# CSM32RV20_TSSOP20_V1_1.net
KiCad netlist of a schematic drawn in Altium Designer
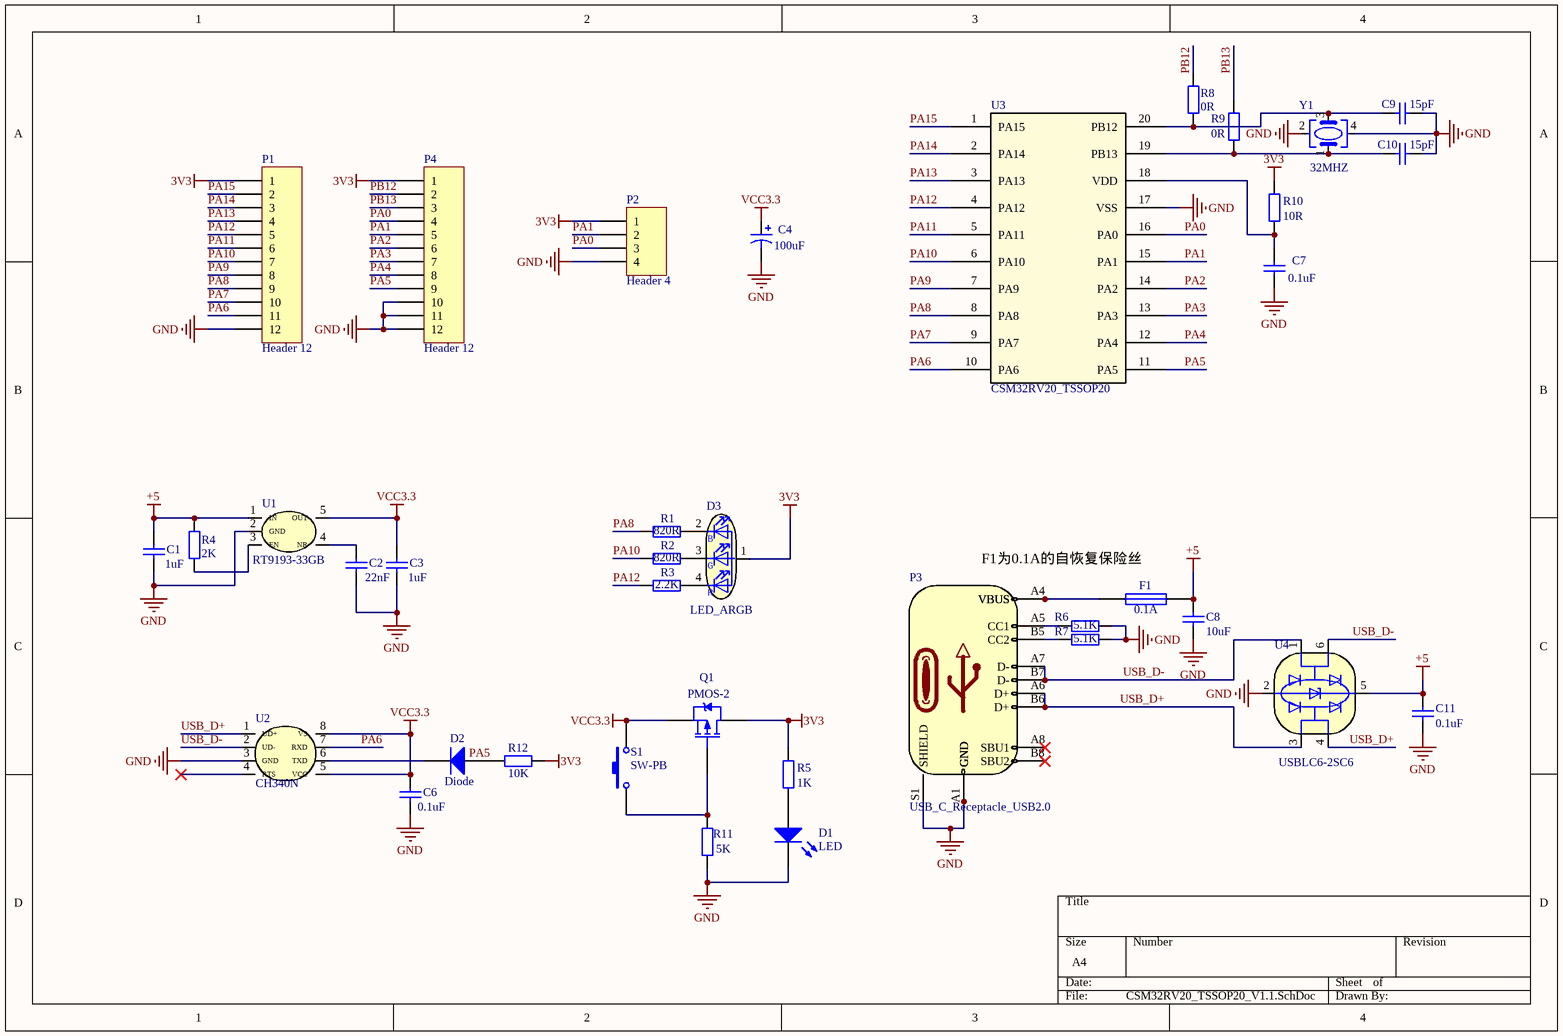
[diagram p0: CSM32RV20_TSSOP20_V1.1.SchDoc]

(export (version "E")
  (design (tool "Eeschema 10.0.6"))
  (components
    (comp (ref "C1")
      (value "1uF")
      (footprint "0402")
      (description "Capacitor")
      (fields (field (name "PUBLISHER") "Altium Limited"))
      (libsource (lib "Miscellaneous Devices") (part "Cap"))
    )
    (comp (ref "C2")
      (value "22nF")
      (footprint "0402")
      (description "Capacitor")
      (fields (field (name "PUBLISHER") "Altium Limited"))
      (libsource (lib "Miscellaneous Devices") (part "Cap"))
    )
    (comp (ref "C3")
      (value "1uF")
      (footprint "0402")
      (description "Capacitor")
      (fields (field (name "PUBLISHER") "Altium Limited"))
      (libsource (lib "Miscellaneous Devices") (part "Cap"))
    )
    (comp (ref "C4")
      (value "100uF")
      (footprint "C1210")
      (description "Polarized Capacitor (Surface Mount)")
      (fields (field (name "PUBLISHER") "Altium Limited"))
      (libsource (lib "Miscellaneous Devices") (part "Cap Pol3"))
    )
    (comp (ref "C6")
      (value "0.1uF")
      (footprint "0402")
      (description "Capacitor")
      (fields (field (name "PUBLISHER") "Altium Limited"))
      (libsource (lib "Miscellaneous Devices") (part "Cap"))
    )
    (comp (ref "C7")
      (value "0.1uF")
      (footprint "0402")
      (description "Capacitor")
      (fields (field (name "PUBLISHER") "Altium Limited"))
      (libsource (lib "Miscellaneous Devices") (part "Cap"))
    )
    (comp (ref "C8")
      (value "10uF")
      (footprint "0402")
      (description "Capacitor")
      (fields (field (name "PUBLISHER") "Altium Limited"))
      (libsource (lib "Miscellaneous Devices") (part "Cap"))
    )
    (comp (ref "C9")
      (value "15pF")
      (footprint "0402")
      (description "Capacitor")
      (fields (field (name "PUBLISHER") "Altium Limited"))
      (libsource (lib "Miscellaneous Devices") (part "Cap"))
    )
    (comp (ref "C10")
      (value "15pF")
      (footprint "0402")
      (description "Capacitor")
      (fields (field (name "PUBLISHER") "Altium Limited"))
      (libsource (lib "Miscellaneous Devices") (part "Cap"))
    )
    (comp (ref "C11")
      (value "0.1uF")
      (footprint "0402")
      (description "Capacitor")
      (fields (field (name "PUBLISHER") "Altium Limited"))
      (libsource (lib "Miscellaneous Devices") (part "Cap"))
    )
    (comp (ref "D1")
      (value "LED")
      (footprint "LED 0402")
      (description "Typical INFRARED GaAs LED")
      (fields (field (name "PUBLISHER") "Altium Limited"))
      (libsource (lib "Miscellaneous Devices") (part "LED0"))
    )
    (comp (ref "D2")
      (value "Diode")
      (footprint "D_SOD-123")
      (description "Default Diode")
      (fields (field (name "PUBLISHER") "Altium Limited"))
      (libsource (lib "Miscellaneous Devices") (part "Diode"))
    )
    (comp (ref "D3")
      (value "LED_ARGB")
      (footprint "LED_RGB_1210")
      (libsource (lib "YYT_library") (part "LED_ARGB"))
    )
    (comp (ref "F1")
      (value "0.1A")
      (footprint "C0805")
      (description "Fuse")
      (fields (field (name "PUBLISHER") "Altium Limited"))
      (libsource (lib "Miscellaneous Devices") (part "Fuse 1"))
    )
    (comp (ref "P1")
      (value "Header 12")
      (footprint "HDR1X12")
      (description "Header, 12-Pin")
      (fields (field (name "PUBLISHER") "Altium Limited"))
      (libsource (lib "Miscellaneous Connectors") (part "Header 12"))
    )
    (comp (ref "P2")
      (value "Header 4")
      (footprint "HDR1X4")
      (description "Header, 4-Pin")
      (fields (field (name "PUBLISHER") "Altium Limited"))
      (libsource (lib "Miscellaneous Connectors") (part "Header 4"))
    )
    (comp (ref "P3")
      (value "USB_C_Receptacle_USB2.0")
      (footprint "USB-C-SMD_KH-TYPE-C-16P")
      (libsource (lib "YYT_library") (part "USB_C_Receptacle_USB2.0"))
    )
    (comp (ref "P4")
      (value "Header 12")
      (footprint "HDR1X12")
      (description "Header, 12-Pin")
      (fields (field (name "PUBLISHER") "Altium Limited"))
      (libsource (lib "Miscellaneous Connectors") (part "Header 12"))
    )
    (comp (ref "Q1")
      (value "PMOS-2")
      (footprint "SOT-23")
      (description "P-Channel Power MOSFET")
      (fields (field (name "PUBLISHER") "Altium Limited"))
      (libsource (lib "YYT_library") (part "PMOS-2"))
    )
    (comp (ref "R1")
      (value "820R")
      (footprint "0402")
      (description "Resistor")
      (fields (field (name "PUBLISHER") "Altium Limited"))
      (libsource (lib "Miscellaneous Devices") (part "Res2"))
    )
    (comp (ref "R2")
      (value "820R")
      (footprint "0402")
      (description "Resistor")
      (fields (field (name "PUBLISHER") "Altium Limited"))
      (libsource (lib "Miscellaneous Devices") (part "Res2"))
    )
    (comp (ref "R3")
      (value "2.2K")
      (footprint "0402")
      (description "Resistor")
      (fields (field (name "PUBLISHER") "Altium Limited"))
      (libsource (lib "Miscellaneous Devices") (part "Res2"))
    )
    (comp (ref "R4")
      (value "2K")
      (footprint "0402")
      (description "Resistor")
      (fields (field (name "PUBLISHER") "Altium Limited"))
      (libsource (lib "") (part "Res2_1"))
    )
    (comp (ref "R5")
      (value "1K")
      (footprint "0402")
      (description "Resistor")
      (fields (field (name "PUBLISHER") "Altium Limited"))
      (libsource (lib "") (part "Res2_1"))
    )
    (comp (ref "R6")
      (value "5.1K")
      (footprint "0402")
      (description "Resistor")
      (fields (field (name "PUBLISHER") "Altium Limited"))
      (libsource (lib "Miscellaneous Devices") (part "Res2"))
    )
    (comp (ref "R7")
      (value "5.1K")
      (footprint "0402")
      (description "Resistor")
      (fields (field (name "PUBLISHER") "Altium Limited"))
      (libsource (lib "Miscellaneous Devices") (part "Res2"))
    )
    (comp (ref "R8")
      (value "0R")
      (footprint "0402")
      (description "Resistor")
      (fields (field (name "PUBLISHER") "Altium Limited"))
      (libsource (lib "") (part "Res2_1"))
    )
    (comp (ref "R9")
      (value "0R")
      (footprint "0402")
      (description "Resistor")
      (fields (field (name "PUBLISHER") "Altium Limited"))
      (libsource (lib "") (part "Res2_1"))
    )
    (comp (ref "R10")
      (value "10R")
      (footprint "0402")
      (description "Resistor")
      (fields (field (name "PUBLISHER") "Altium Limited"))
      (libsource (lib "") (part "Res2_1"))
    )
    (comp (ref "R11")
      (value "5K")
      (footprint "0402")
      (description "Resistor")
      (fields (field (name "PUBLISHER") "Altium Limited"))
      (libsource (lib "") (part "Res2_1"))
    )
    (comp (ref "R12")
      (value "10K")
      (footprint "0402")
      (description "Resistor")
      (fields (field (name "PUBLISHER") "Altium Limited"))
      (libsource (lib "Miscellaneous Devices") (part "Res2"))
    )
    (comp (ref "S1")
      (value "SW-PB")
      (footprint "SW_PUSH_SPST_NO_ALPS_SKRK")
      (description "Switch")
      (fields (field (name "PUBLISHER") "Altium Limited"))
      (libsource (lib "Miscellaneous Devices") (part "SW-PB"))
    )
    (comp (ref "U1")
      (value "RT9193-33GB")
      (footprint "SOT-23-5")
      (libsource (lib "YYT_library") (part "RT9193-33GB"))
    )
    (comp (ref "U2")
      (value "CH340N")
      (footprint "SOP-8-1EP_6X5MM_P1.27MM")
      (libsource (lib "YYT_library") (part "CH340N"))
    )
    (comp (ref "U3")
      (value "CSM32RV20_TSSOP20")
      (footprint "CSM32RV20_TSSOP20")
      (libsource (lib "YYT_library") (part "CSM32RV20_TSSOP20_1"))
    )
    (comp (ref "U4")
      (value "USBLC6-2SC6")
      (footprint "SOT-23-6")
      (libsource (lib "YYT_library") (part "USBLC6-2SC6"))
    )
    (comp (ref "Y1")
      (value "32MHZ")
      (footprint "CRYSTAL_SMD_3225-4PIN_3.2X2.5MM")
      (libsource (lib "YYT_library") (part "Crystal"))
    )
  )
  (nets
    (net (code "1") (name "+5") (class "Default")
      (node (ref "C1") (pin "2") (pinfunction "2_2") (pintype "passive"))
      (node (ref "C11") (pin "2") (pinfunction "2_2") (pintype "passive"))
      (node (ref "C8") (pin "2") (pinfunction "2_2") (pintype "passive"))
      (node (ref "F1") (pin "2") (pinfunction "2_2") (pintype "passive"))
      (node (ref "R4") (pin "2") (pinfunction "2_2") (pintype "passive"))
      (node (ref "U1") (pin "1") (pinfunction "IN_1") (pintype "passive"))
      (node (ref "U4") (pin "5") (pinfunction "VBUS_5") (pintype "passive"))
    )
    (net (code "2") (name "/PA0") (class "Default")
      (node (ref "P2") (pin "3") (pinfunction "3_3") (pintype "passive"))
      (node (ref "P4") (pin "4") (pinfunction "4_4") (pintype "passive"))
      (node (ref "U3") (pin "16") (pinfunction "PA0_16") (pintype "passive"))
    )
    (net (code "3") (name "/PA1") (class "Default")
      (node (ref "P2") (pin "2") (pinfunction "2_2") (pintype "passive"))
      (node (ref "P4") (pin "5") (pinfunction "5_5") (pintype "passive"))
      (node (ref "U3") (pin "15") (pinfunction "PA1_15") (pintype "passive"))
    )
    (net (code "4") (name "/PA2") (class "Default")
      (node (ref "P4") (pin "6") (pinfunction "6_6") (pintype "passive"))
      (node (ref "U3") (pin "14") (pinfunction "PA2_14") (pintype "passive"))
    )
    (net (code "5") (name "/PA3") (class "Default")
      (node (ref "P4") (pin "7") (pinfunction "7_7") (pintype "passive"))
      (node (ref "U3") (pin "13") (pinfunction "PA3_13") (pintype "passive"))
    )
    (net (code "6") (name "/PA4") (class "Default")
      (node (ref "P4") (pin "8") (pinfunction "8_8") (pintype "passive"))
      (node (ref "U3") (pin "12") (pinfunction "PA4_12") (pintype "passive"))
    )
    (net (code "7") (name "/PA5") (class "Default")
      (node (ref "D2") (pin "1") (pinfunction "A_1") (pintype "passive"))
      (node (ref "P4") (pin "9") (pinfunction "9_9") (pintype "passive"))
      (node (ref "R12") (pin "1") (pinfunction "1_1") (pintype "passive"))
      (node (ref "U3") (pin "11") (pinfunction "PA5_11") (pintype "passive"))
    )
    (net (code "8") (name "/PA6") (class "Default")
      (node (ref "P1") (pin "11") (pinfunction "11_11") (pintype "passive"))
      (node (ref "U2") (pin "7") (pinfunction "RXD_7") (pintype "passive"))
      (node (ref "U3") (pin "10") (pinfunction "PA6_10") (pintype "passive"))
    )
    (net (code "9") (name "/PA7") (class "Default")
      (node (ref "P1") (pin "10") (pinfunction "10_10") (pintype "passive"))
      (node (ref "U3") (pin "9") (pinfunction "PA7_9") (pintype "passive"))
    )
    (net (code "10") (name "/PA8") (class "Default")
      (node (ref "P1") (pin "9") (pinfunction "9_9") (pintype "passive"))
      (node (ref "R1") (pin "1") (pinfunction "1_1") (pintype "passive"))
      (node (ref "U3") (pin "8") (pinfunction "PA8_8") (pintype "passive"))
    )
    (net (code "11") (name "/PA9") (class "Default")
      (node (ref "P1") (pin "8") (pinfunction "8_8") (pintype "passive"))
      (node (ref "U3") (pin "7") (pinfunction "PA9_7") (pintype "passive"))
    )
    (net (code "12") (name "/PA10") (class "Default")
      (node (ref "P1") (pin "7") (pinfunction "7_7") (pintype "passive"))
      (node (ref "R2") (pin "1") (pinfunction "1_1") (pintype "passive"))
      (node (ref "U3") (pin "6") (pinfunction "PA10_6") (pintype "passive"))
    )
    (net (code "13") (name "/PA11") (class "Default")
      (node (ref "P1") (pin "6") (pinfunction "6_6") (pintype "passive"))
      (node (ref "U3") (pin "5") (pinfunction "PA11_5") (pintype "passive"))
    )
    (net (code "14") (name "/PA12") (class "Default")
      (node (ref "P1") (pin "5") (pinfunction "5_5") (pintype "passive"))
      (node (ref "R3") (pin "1") (pinfunction "1_1") (pintype "passive"))
      (node (ref "U3") (pin "4") (pinfunction "PA12_4") (pintype "passive"))
    )
    (net (code "15") (name "/PA13") (class "Default")
      (node (ref "P1") (pin "4") (pinfunction "4_4") (pintype "passive"))
      (node (ref "U3") (pin "3") (pinfunction "PA13_3") (pintype "passive"))
    )
    (net (code "16") (name "/PA14") (class "Default")
      (node (ref "P1") (pin "3") (pinfunction "3_3") (pintype "passive"))
      (node (ref "U3") (pin "2") (pinfunction "PA14_2") (pintype "passive"))
    )
    (net (code "17") (name "/PA15") (class "Default")
      (node (ref "P1") (pin "2") (pinfunction "2_2") (pintype "passive"))
      (node (ref "U3") (pin "1") (pinfunction "PA15_1") (pintype "passive"))
    )
    (net (code "18") (name "/PB12") (class "Default")
      (node (ref "P4") (pin "2") (pinfunction "2_2") (pintype "passive"))
      (node (ref "R8") (pin "2") (pinfunction "2_2") (pintype "passive"))
    )
    (net (code "19") (name "/PB13") (class "Default")
      (node (ref "P4") (pin "3") (pinfunction "3_3") (pintype "passive"))
      (node (ref "R9") (pin "2") (pinfunction "2_2") (pintype "passive"))
    )
    (net (code "20") (name "/USB_D+") (class "Default")
      (node (ref "P3") (pin "A6") (pinfunction "D+_A6") (pintype "passive"))
      (node (ref "P3") (pin "B6") (pinfunction "D+_B6") (pintype "passive"))
      (node (ref "U2") (pin "1") (pinfunction "UD+_1") (pintype "passive"))
      (node (ref "U4") (pin "3") (pinfunction "I/O2_3") (pintype "passive"))
      (node (ref "U4") (pin "4") (pinfunction "I/O2_4") (pintype "passive"))
    )
    (net (code "21") (name "/USB_D-") (class "Default")
      (node (ref "P3") (pin "A7") (pinfunction "D-_A7") (pintype "passive"))
      (node (ref "P3") (pin "B7") (pinfunction "D-_B7") (pintype "passive"))
      (node (ref "U2") (pin "2") (pinfunction "UD-_2") (pintype "passive"))
      (node (ref "U4") (pin "1") (pinfunction "I/O1_1") (pintype "passive"))
      (node (ref "U4") (pin "6") (pinfunction "I/O1_6") (pintype "passive"))
    )
    (net (code "22") (name "3V3") (class "Default")
      (node (ref "D3") (pin "1") (pinfunction "A_1") (pintype "passive"))
      (node (ref "P1") (pin "1") (pinfunction "1_1") (pintype "passive"))
      (node (ref "P2") (pin "1") (pinfunction "1_1") (pintype "passive"))
      (node (ref "P4") (pin "1") (pinfunction "1_1") (pintype "passive"))
      (node (ref "Q1") (pin "3") (pinfunction "D_3") (pintype "passive"))
      (node (ref "R10") (pin "2") (pinfunction "2_2") (pintype "passive"))
      (node (ref "R12") (pin "2") (pinfunction "2_2") (pintype "passive"))
      (node (ref "R5") (pin "2") (pinfunction "2_2") (pintype "passive"))
    )
    (net (code "23") (name "GND") (class "Default")
      (node (ref "C1") (pin "1") (pinfunction "1_1") (pintype "passive"))
      (node (ref "C10") (pin "2") (pinfunction "2_2") (pintype "passive"))
      (node (ref "C11") (pin "1") (pinfunction "1_1") (pintype "passive"))
      (node (ref "C2") (pin "1") (pinfunction "1_1") (pintype "passive"))
      (node (ref "C3") (pin "1") (pinfunction "1_1") (pintype "passive"))
      (node (ref "C4") (pin "2") (pinfunction "2_2") (pintype "passive"))
      (node (ref "C6") (pin "1") (pinfunction "1_1") (pintype "passive"))
      (node (ref "C7") (pin "1") (pinfunction "1_1") (pintype "passive"))
      (node (ref "C8") (pin "1") (pinfunction "1_1") (pintype "passive"))
      (node (ref "C9") (pin "2") (pinfunction "2_2") (pintype "passive"))
      (node (ref "D1") (pin "2") (pinfunction "K_2") (pintype "passive"))
      (node (ref "P1") (pin "12") (pinfunction "12_12") (pintype "passive"))
      (node (ref "P2") (pin "4") (pinfunction "4_4") (pintype "passive"))
      (node (ref "P3") (pin "A1") (pinfunction "GND_A1") (pintype "passive"))
      (node (ref "P3") (pin "A12") (pinfunction "GND_A12") (pintype "passive"))
      (node (ref "P3") (pin "B1") (pinfunction "GND_B1") (pintype "passive"))
      (node (ref "P3") (pin "B12") (pinfunction "GND_B12") (pintype "passive"))
      (node (ref "P3") (pin "S1") (pinfunction "SHIELD_S1") (pintype "passive"))
      (node (ref "P4") (pin "10") (pinfunction "10_10") (pintype "passive"))
      (node (ref "P4") (pin "11") (pinfunction "11_11") (pintype "passive"))
      (node (ref "P4") (pin "12") (pinfunction "12_12") (pintype "passive"))
      (node (ref "R11") (pin "1") (pinfunction "1_1") (pintype "passive"))
      (node (ref "R6") (pin "2") (pinfunction "2_2") (pintype "passive"))
      (node (ref "R7") (pin "2") (pinfunction "2_2") (pintype "passive"))
      (node (ref "U1") (pin "2") (pinfunction "GND_2") (pintype "passive"))
      (node (ref "U2") (pin "3") (pinfunction "GND_3") (pintype "passive"))
      (node (ref "U3") (pin "17") (pinfunction "VSS_17") (pintype "passive"))
      (node (ref "U4") (pin "2") (pinfunction "GND_2") (pintype "passive"))
      (node (ref "Y1") (pin "2") (pinfunction "2_2") (pintype "passive"))
      (node (ref "Y1") (pin "4") (pinfunction "4_4") (pintype "passive"))
    )
    (net (code "24") (name "Net-(D1-A)") (class "Default")
      (node (ref "D1") (pin "1") (pinfunction "A_1") (pintype "passive"))
      (node (ref "R5") (pin "1") (pinfunction "1_1") (pintype "passive"))
    )
    (net (code "25") (name "Net-(D2-K)") (class "Default")
      (node (ref "D2") (pin "2") (pinfunction "K_2") (pintype "passive"))
      (node (ref "U2") (pin "6") (pinfunction "TXD_6") (pintype "passive"))
    )
    (net (code "26") (name "Net-(D3-BK)") (class "Default")
      (node (ref "D3") (pin "4") (pinfunction "BK_4") (pintype "passive"))
      (node (ref "R3") (pin "2") (pinfunction "2_2") (pintype "passive"))
    )
    (net (code "27") (name "Net-(D3-GK)") (class "Default")
      (node (ref "D3") (pin "3") (pinfunction "GK_3") (pintype "passive"))
      (node (ref "R2") (pin "2") (pinfunction "2_2") (pintype "passive"))
    )
    (net (code "28") (name "Net-(D3-RK)") (class "Default")
      (node (ref "D3") (pin "2") (pinfunction "RK_2") (pintype "passive"))
      (node (ref "R1") (pin "2") (pinfunction "2_2") (pintype "passive"))
    )
    (net (code "29") (name "Net-(F1-Pad1)") (class "Default")
      (node (ref "F1") (pin "1") (pinfunction "1_1") (pintype "passive"))
      (node (ref "P3") (pin "A4") (pinfunction "VBUS_A4") (pintype "passive"))
      (node (ref "P3") (pin "A9") (pinfunction "VBUS_A9") (pintype "passive"))
      (node (ref "P3") (pin "B4") (pinfunction "VBUS_B4") (pintype "passive"))
      (node (ref "P3") (pin "B9") (pinfunction "VBUS_B9") (pintype "passive"))
    )
    (net (code "30") (name "Net-(P3-CC1)") (class "Default")
      (node (ref "P3") (pin "A5") (pinfunction "CC1_A5") (pintype "passive"))
      (node (ref "R6") (pin "1") (pinfunction "1_1") (pintype "passive"))
    )
    (net (code "31") (name "Net-(P3-CC2)") (class "Default")
      (node (ref "P3") (pin "B5") (pinfunction "CC2_B5") (pintype "passive"))
      (node (ref "R7") (pin "1") (pinfunction "1_1") (pintype "passive"))
    )
    (net (code "32") (name "Net-(Q1-G)") (class "Default")
      (node (ref "Q1") (pin "1") (pinfunction "G_1") (pintype "passive"))
      (node (ref "R11") (pin "2") (pinfunction "2_2") (pintype "passive"))
      (node (ref "S1") (pin "1") (pinfunction "1_1") (pintype "passive"))
    )
    (net (code "33") (name "Net-(U1-EN)") (class "Default")
      (node (ref "R4") (pin "1") (pinfunction "1_1") (pintype "passive"))
      (node (ref "U1") (pin "3") (pinfunction "EN_3") (pintype "passive"))
    )
    (net (code "34") (name "Net-(U1-NR)") (class "Default")
      (node (ref "C2") (pin "2") (pinfunction "2_2") (pintype "passive"))
      (node (ref "U1") (pin "4") (pinfunction "NR_4") (pintype "passive"))
    )
    (net (code "35") (name "Net-(U3-PB12)") (class "Default")
      (node (ref "C9") (pin "1") (pinfunction "1_1") (pintype "passive"))
      (node (ref "R8") (pin "1") (pinfunction "1_1") (pintype "passive"))
      (node (ref "U3") (pin "20") (pinfunction "PB12_20") (pintype "passive"))
      (node (ref "Y1") (pin "3") (pinfunction "3_3") (pintype "passive"))
    )
    (net (code "36") (name "Net-(U3-PB13)") (class "Default")
      (node (ref "C10") (pin "1") (pinfunction "1_1") (pintype "passive"))
      (node (ref "R9") (pin "1") (pinfunction "1_1") (pintype "passive"))
      (node (ref "U3") (pin "19") (pinfunction "PB13_19") (pintype "passive"))
      (node (ref "Y1") (pin "1") (pinfunction "1_1") (pintype "passive"))
    )
    (net (code "37") (name "Net-(U3-VDD)") (class "Default")
      (node (ref "C7") (pin "2") (pinfunction "2_2") (pintype "passive"))
      (node (ref "R10") (pin "1") (pinfunction "1_1") (pintype "passive"))
      (node (ref "U3") (pin "18") (pinfunction "VDD_18") (pintype "passive"))
    )
    (net (code "38") (name "VCC3.3") (class "Default")
      (node (ref "C3") (pin "2") (pinfunction "2_2") (pintype "passive"))
      (node (ref "C4") (pin "1") (pinfunction "1_1") (pintype "passive"))
      (node (ref "C6") (pin "2") (pinfunction "2_2") (pintype "passive"))
      (node (ref "Q1") (pin "2") (pinfunction "S_2") (pintype "passive"))
      (node (ref "S1") (pin "2") (pinfunction "2_2") (pintype "passive"))
      (node (ref "U1") (pin "5") (pinfunction "OUT_5") (pintype "passive"))
      (node (ref "U2") (pin "5") (pinfunction "VCC_5") (pintype "passive"))
      (node (ref "U2") (pin "8") (pinfunction "V3_8") (pintype "passive"))
    )
    (net (code "39") (name "unconnected-(P3-SBU1-PadA8)") (class "Default")
      (node (ref "P3") (pin "A8") (pinfunction "SBU1_A8") (pintype "passive+no_connect"))
    )
    (net (code "40") (name "unconnected-(P3-SBU2-PadB8)") (class "Default")
      (node (ref "P3") (pin "B8") (pinfunction "SBU2_B8") (pintype "passive+no_connect"))
    )
    (net (code "41") (name "unconnected-(U2-RTS-Pad4)") (class "Default")
      (node (ref "U2") (pin "4") (pinfunction "RTS_4") (pintype "passive+no_connect"))
    )
  )
)
